# Speedy_V2_1.net
KiCad netlist of a schematic drawn in EAGLE
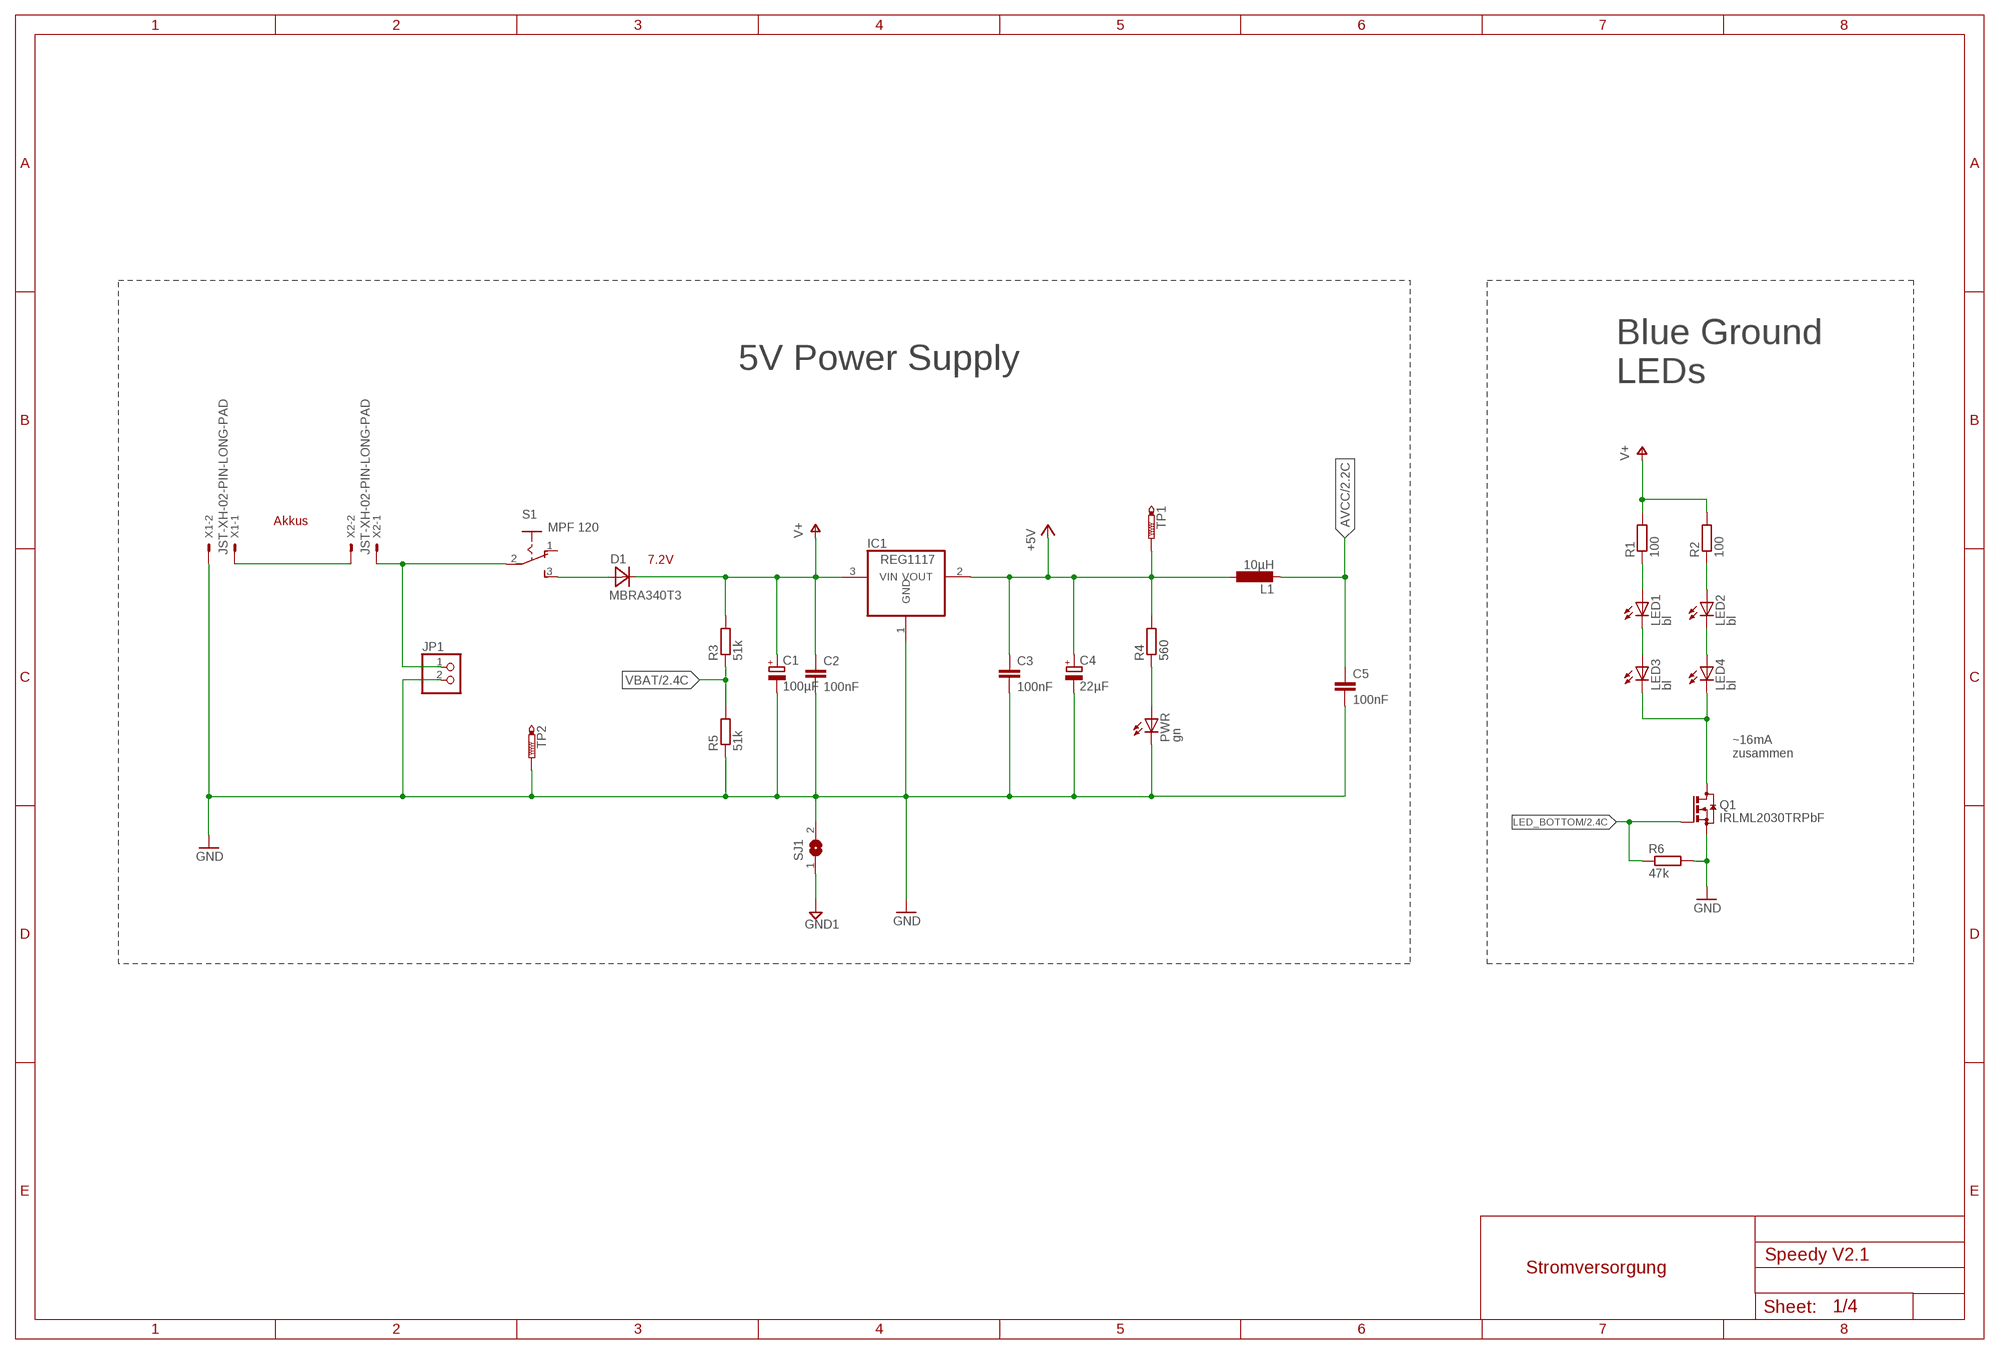
[diagram p0: schematic, sheet 1]
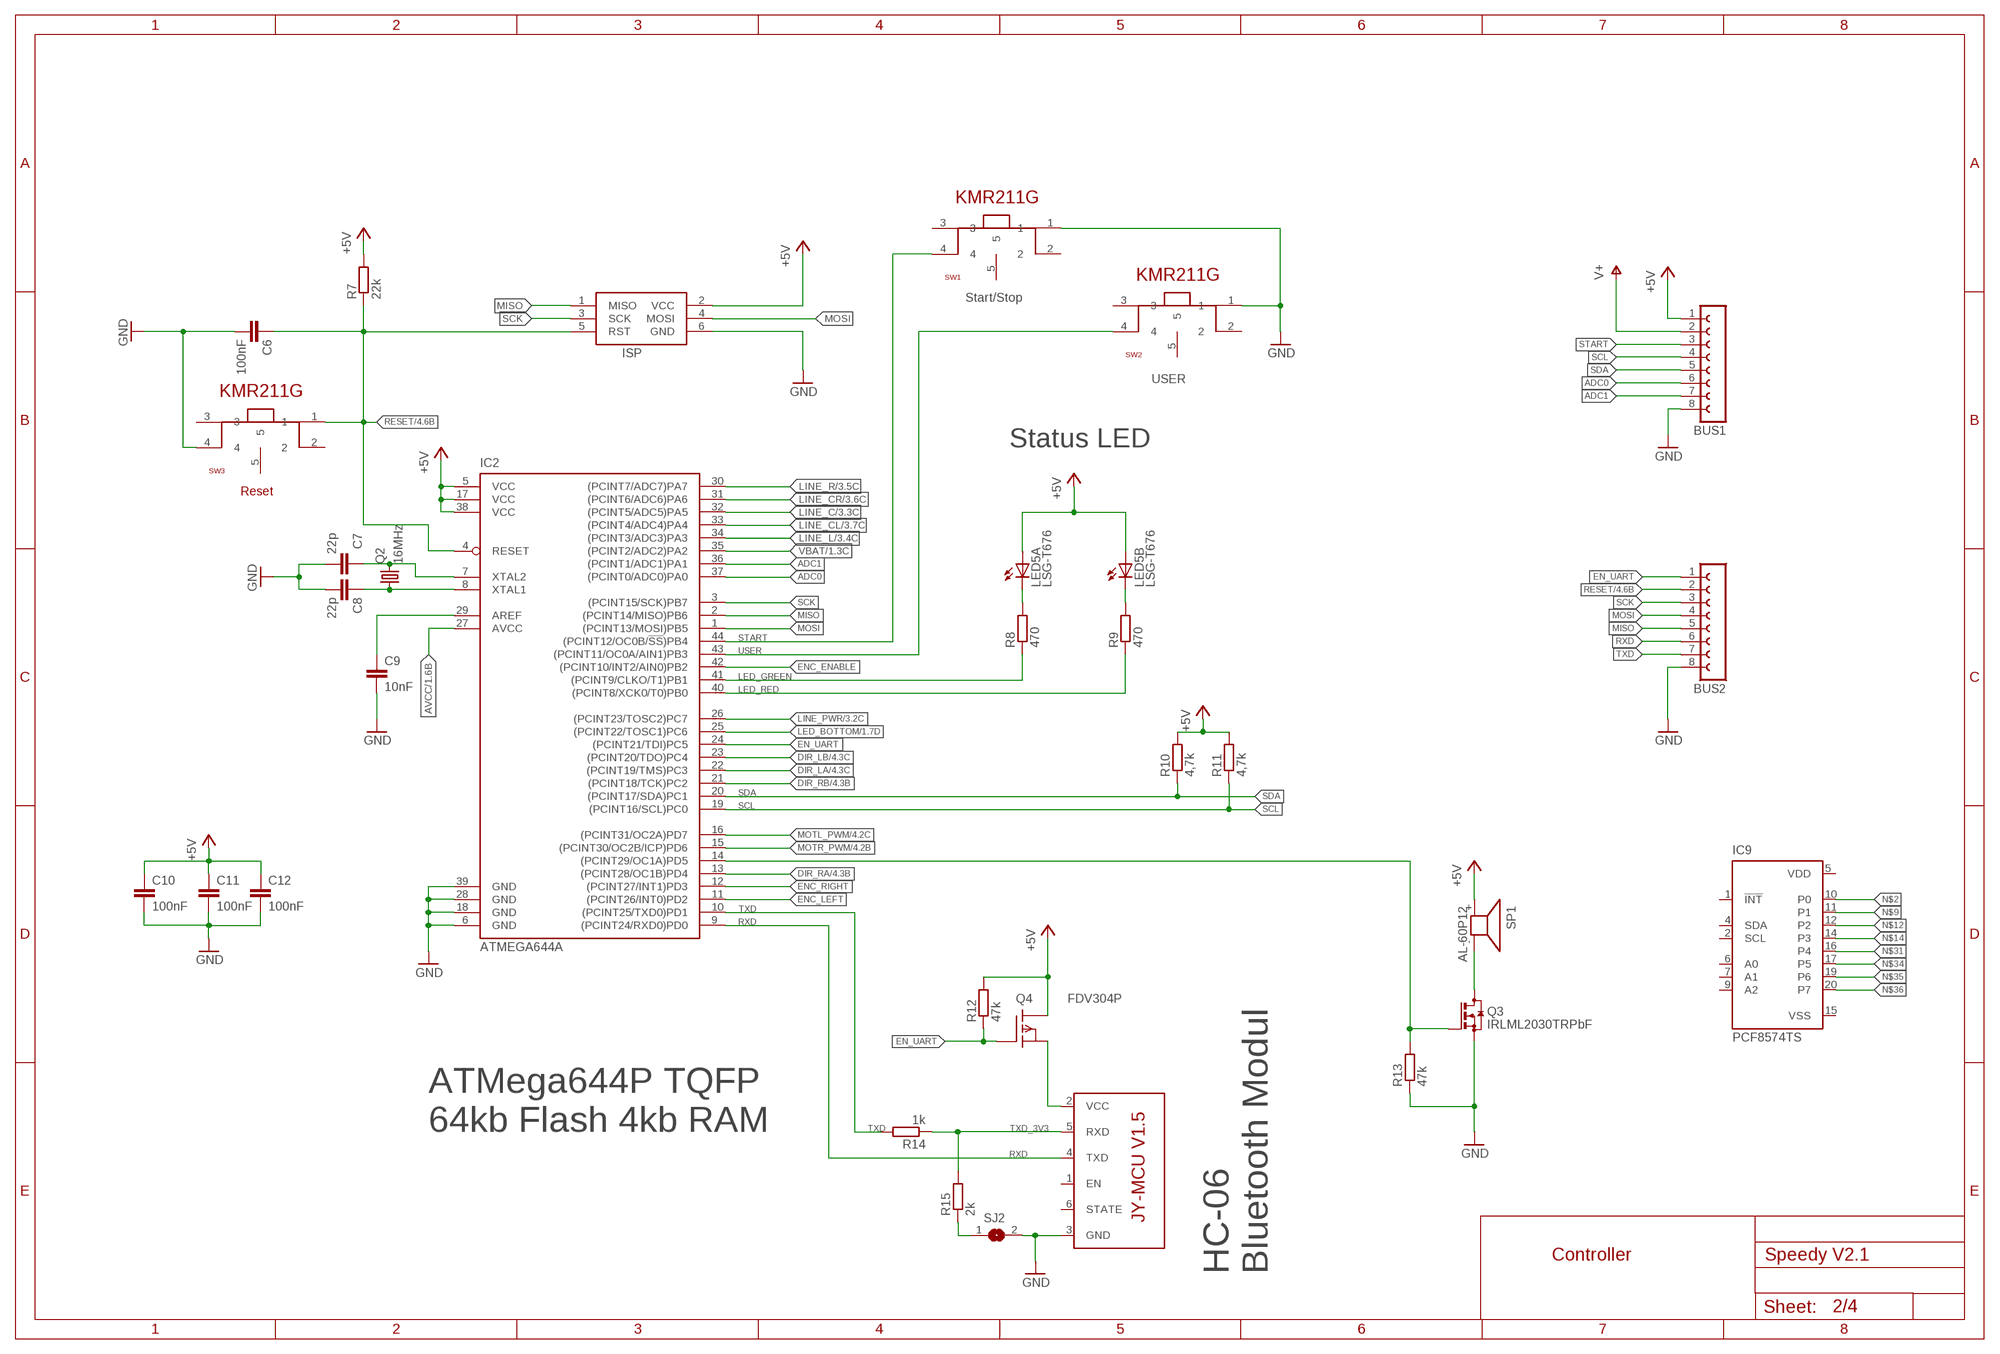
[diagram p1: schematic, sheet 2]
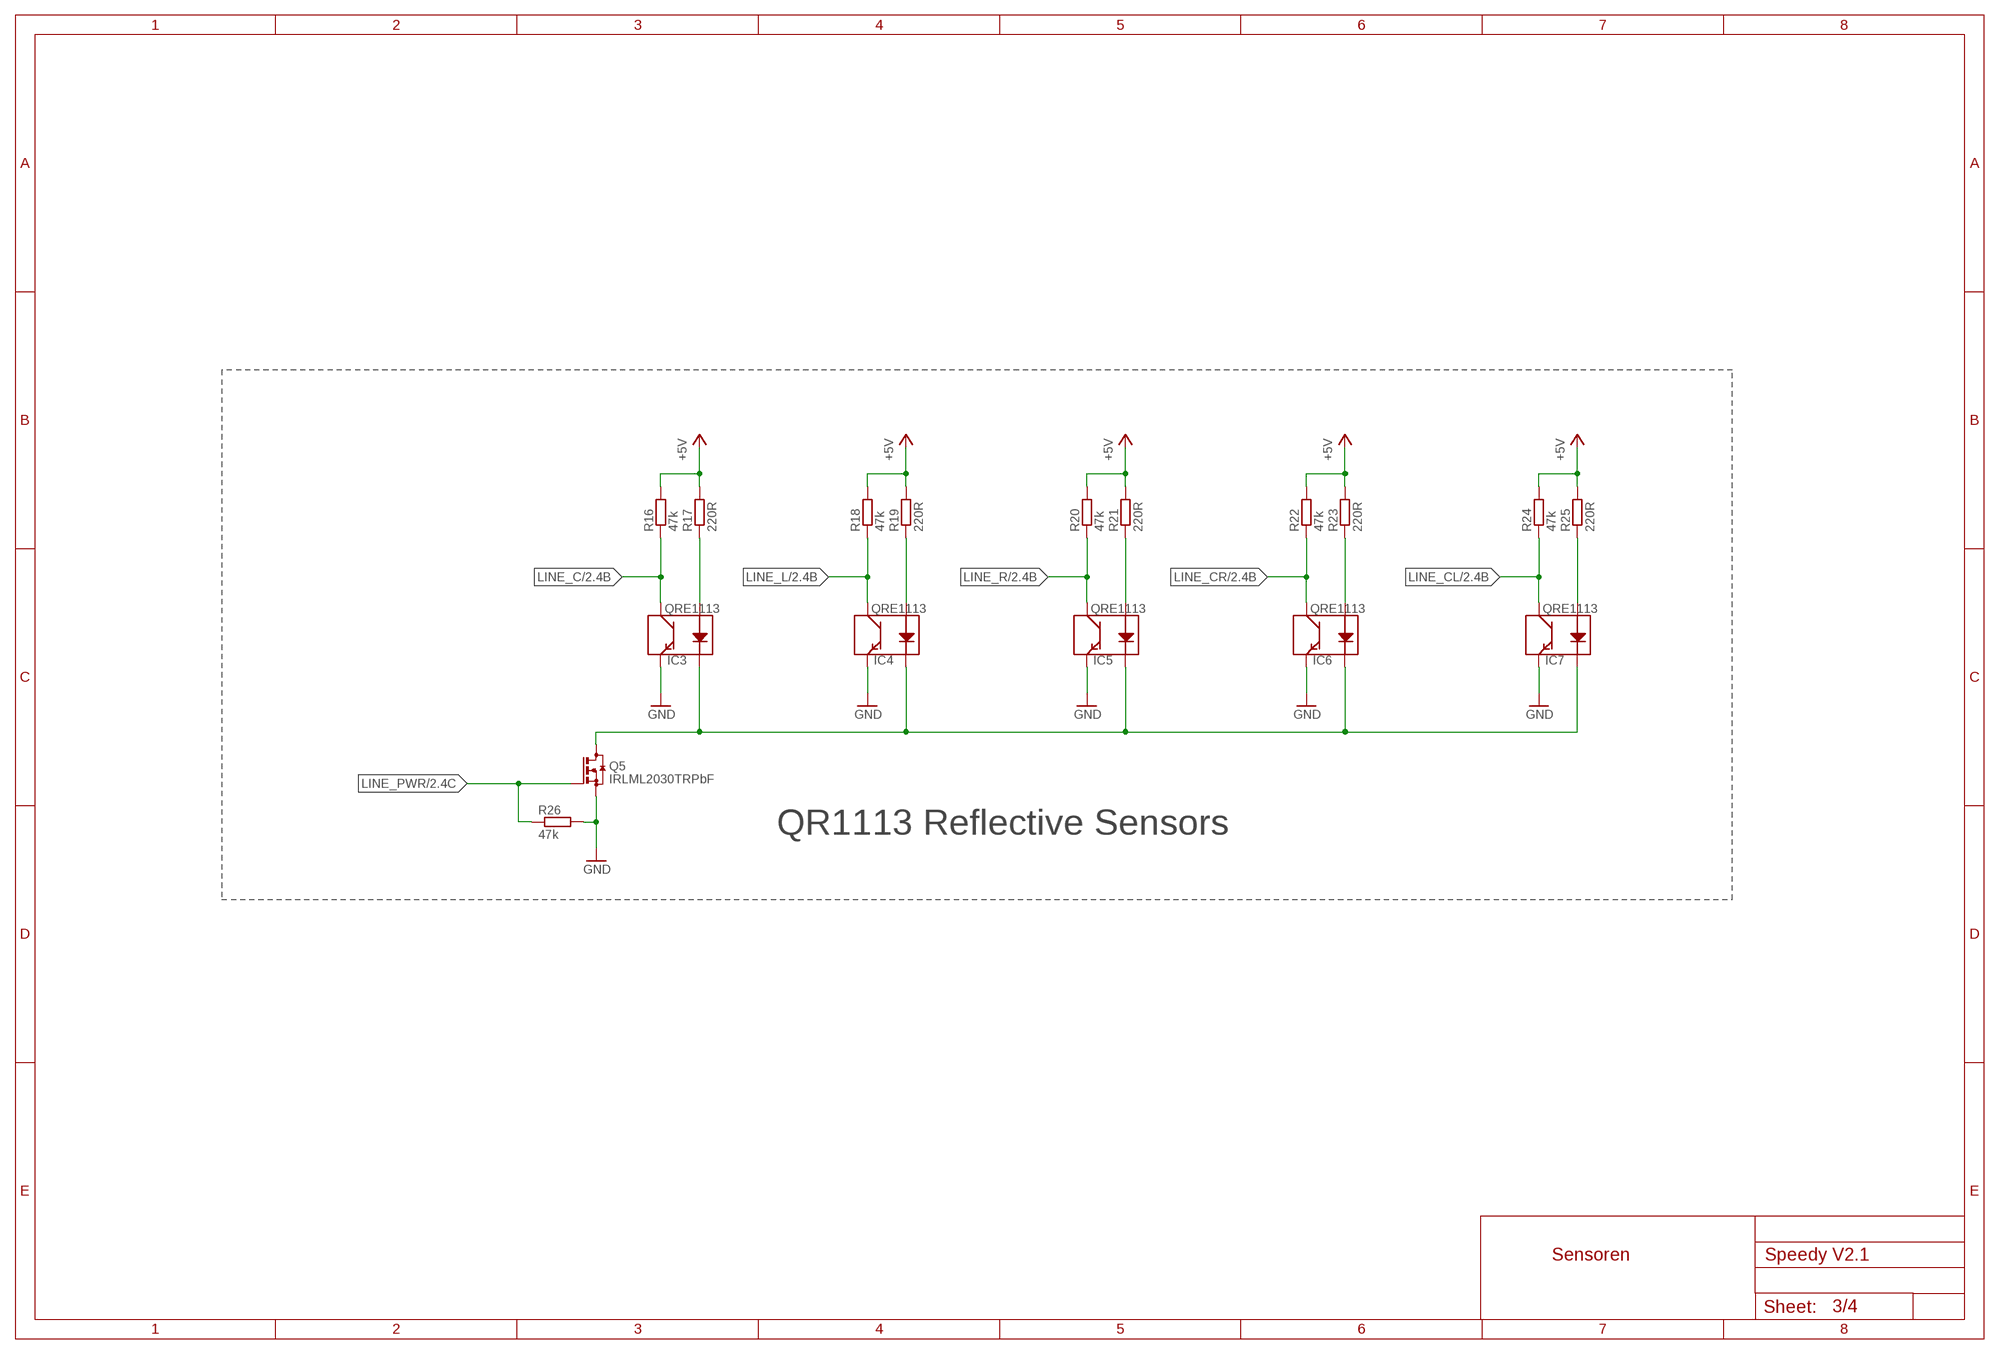
[diagram p2: schematic, sheet 3]
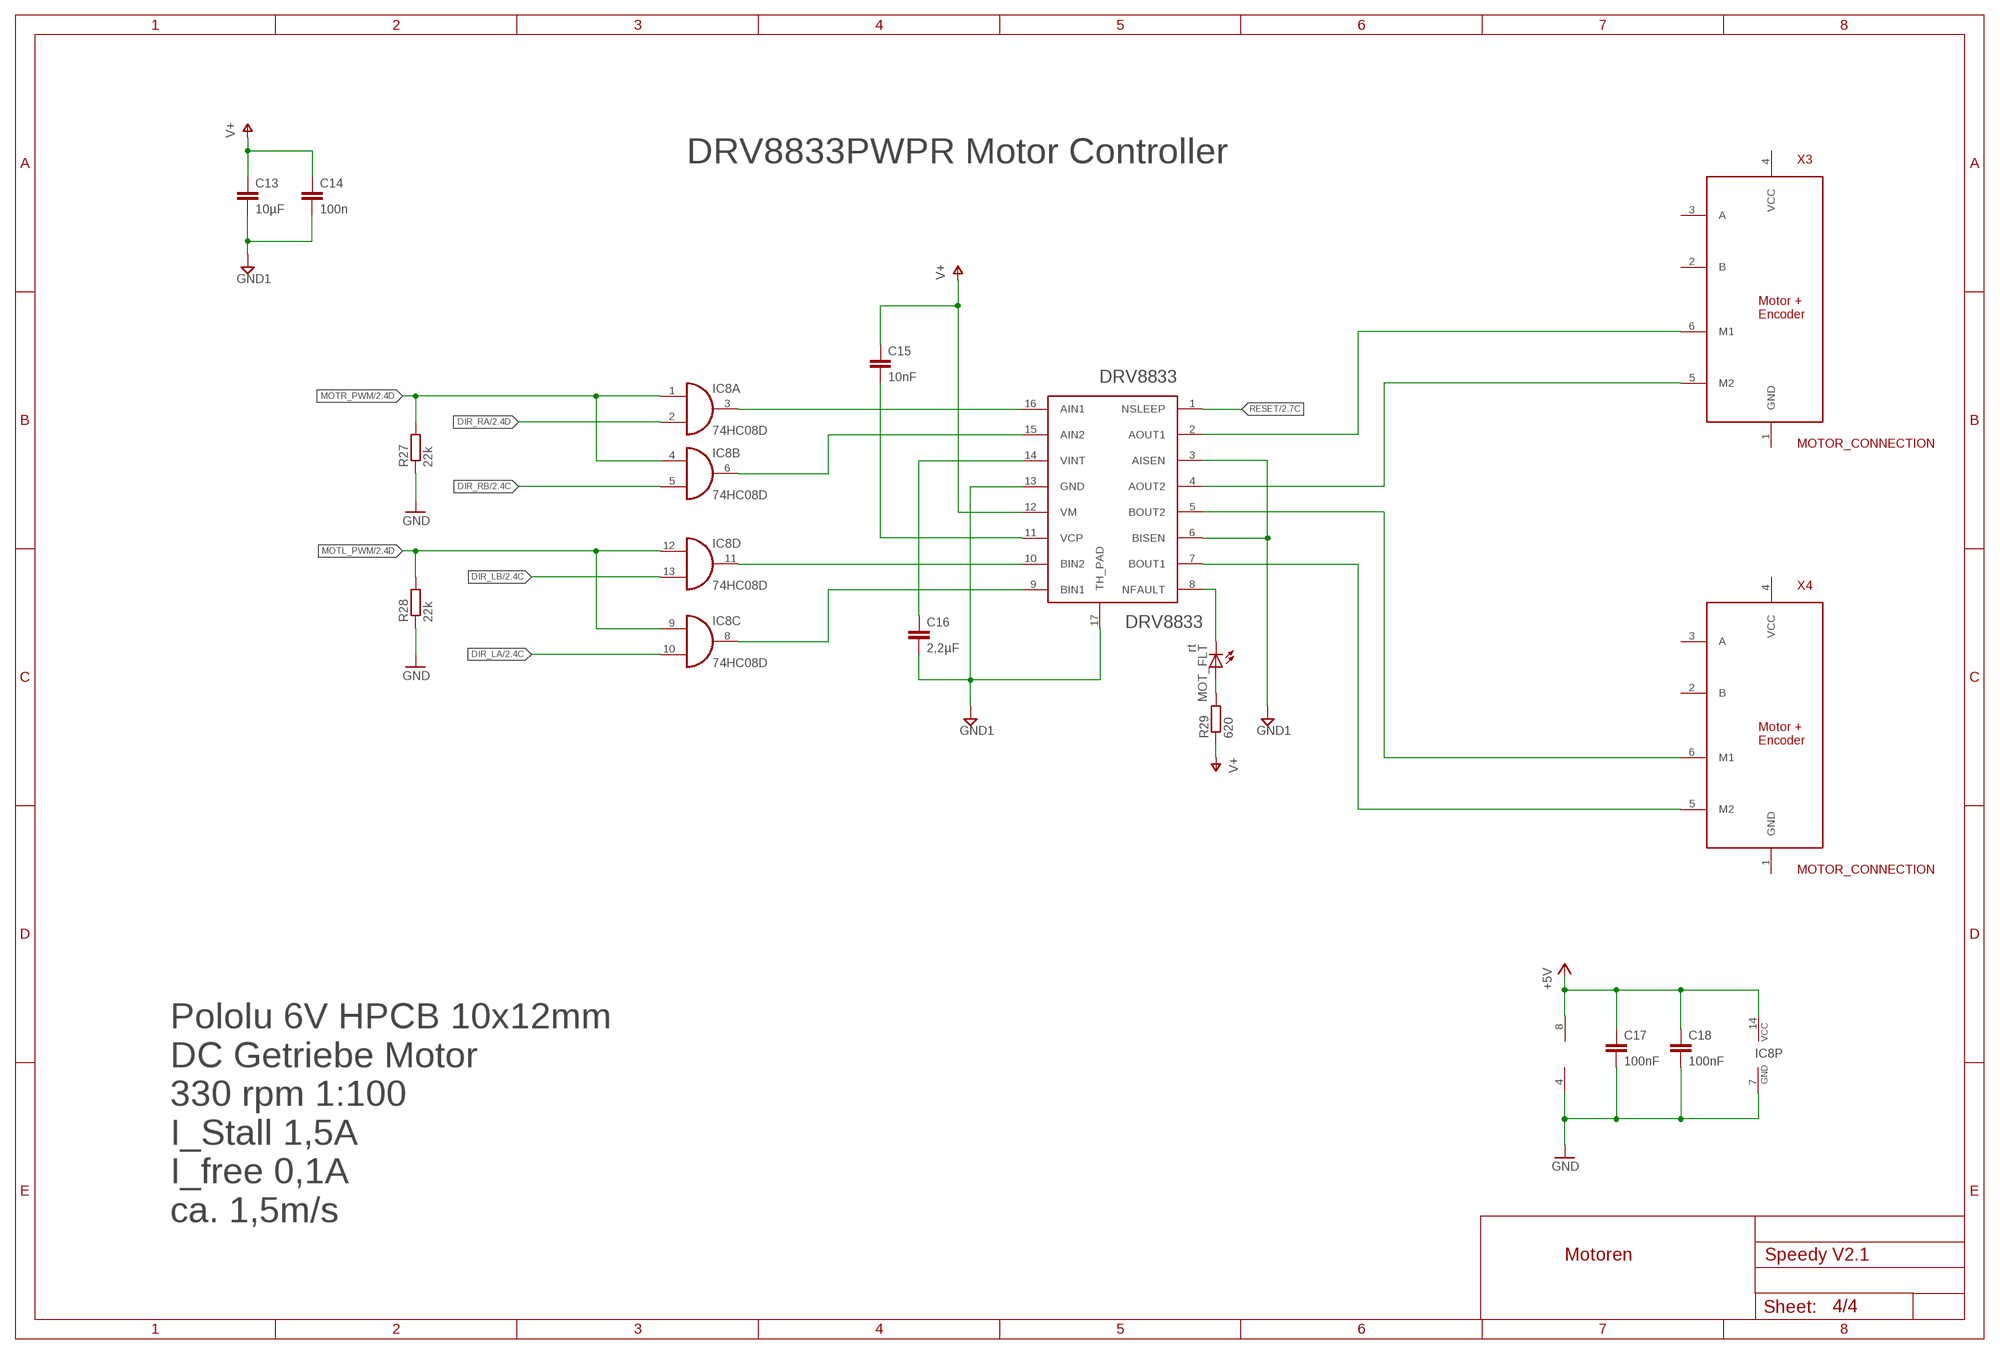
[diagram p3: schematic, sheet 4]

(export (version "E")
  (design (tool "Eeschema 10.0.6"))
  (components
    (comp (ref "C13")
      (value "10µF")
      (footprint "eagle-import:C1206")
      (libsource (lib "eagle-import") (part "C-EUC1206"))
    )
    (comp (ref "C14")
      (value "100n")
      (footprint "eagle-import:C0805")
      (libsource (lib "eagle-import") (part "C-EUC0805"))
    )
    (comp (ref "C15")
      (value "10nF")
      (footprint "eagle-import:C0805")
      (libsource (lib "eagle-import") (part "C-EUC0805"))
    )
    (comp (ref "C16")
      (value "2,2µF")
      (footprint "eagle-import:C1206")
      (libsource (lib "eagle-import") (part "C-EUC1206"))
    )
    (comp (ref "C17")
      (value "100nF")
      (footprint "eagle-import:C0805")
      (libsource (lib "eagle-import") (part "C-EUC0805"))
    )
    (comp (ref "C18")
      (value "100nF")
      (footprint "eagle-import:C0805")
      (libsource (lib "eagle-import") (part "C-EUC0805"))
    )
    (comp (ref "IC8")
      (value "74HC08D")
      (footprint "eagle-import:SO14")
      (libsource (lib "eagle-import") (part "7408DHC"))
    )
    (comp (ref "IC11")
      (value "LM358D")
      (footprint "eagle-import:SO08")
      (libsource (lib "eagle-import") (part "LM358D"))
    )
    (comp (ref "MOT_FLT")
      (value "rt")
      (footprint "eagle-import:CHIP-LED0805")
      (libsource (lib "eagle-import") (part "LEDCHIP-LED0805"))
    )
    (comp (ref "R27")
      (value "22k")
      (footprint "eagle-import:R0805")
      (libsource (lib "eagle-import") (part "R-EU_R0805"))
    )
    (comp (ref "R28")
      (value "22k")
      (footprint "eagle-import:R0805")
      (libsource (lib "eagle-import") (part "R-EU_R0805"))
    )
    (comp (ref "R29")
      (value "620")
      (footprint "eagle-import:R0805")
      (libsource (lib "eagle-import") (part "R-EU_R0805"))
    )
    (comp (ref "U3")
      (value "DRV8833")
      (footprint "eagle-import:SOP65P640X120-17N")
      (libsource (lib "eagle-import") (part "DRV8833"))
    )
    (comp (ref "X3")
      (value "MOTOR_CONNECTION")
      (footprint "eagle-import:2X03")
      (libsource (lib "eagle-import") (part "MOTOR_CONNECTION"))
    )
    (comp (ref "X4")
      (value "MOTOR_CONNECTION")
      (footprint "eagle-import:2X03")
      (libsource (lib "eagle-import") (part "MOTOR_CONNECTION"))
    )
    (comp (ref "BUS1")
      (value "FE08-1")
      (footprint "eagle-import:FE08")
      (libsource (lib "eagle-import") (part "FE08-1"))
    )
    (comp (ref "BUS2")
      (value "FE08-1")
      (footprint "eagle-import:FE08")
      (libsource (lib "eagle-import") (part "FE08-1"))
    )
    (comp (ref "C6")
      (value "100nF")
      (footprint "eagle-import:C0805")
      (libsource (lib "eagle-import") (part "C-EUC0805"))
    )
    (comp (ref "C7")
      (value "22p")
      (footprint "eagle-import:C0603")
      (libsource (lib "eagle-import") (part "C-EUC0603"))
    )
    (comp (ref "C8")
      (value "22p")
      (footprint "eagle-import:C0603")
      (libsource (lib "eagle-import") (part "C-EUC0603"))
    )
    (comp (ref "C9")
      (value "10nF")
      (footprint "eagle-import:C0603")
      (libsource (lib "eagle-import") (part "C-EUC0603"))
    )
    (comp (ref "C10")
      (value "100nF")
      (footprint "eagle-import:C0603")
      (libsource (lib "eagle-import") (part "C-EUC0603"))
    )
    (comp (ref "C11")
      (value "100nF")
      (footprint "eagle-import:C0603")
      (libsource (lib "eagle-import") (part "C-EUC0603"))
    )
    (comp (ref "C12")
      (value "100nF")
      (footprint "eagle-import:C0603")
      (libsource (lib "eagle-import") (part "C-EUC0603"))
    )
    (comp (ref "IC2")
      (value "ATMEGA644A")
      (footprint "eagle-import:TQFP44")
      (fields (field (name "MPN") "ATMEGA644PV-10AU"))
      (libsource (lib "eagle-import") (part "ATMEGA644A"))
    )
    (comp (ref "IC9")
      (value "PCF8574TS")
      (footprint "eagle-import:SSOP20")
      (fields (field (name "MPN") "PCF8574TS/3,118"))
      (libsource (lib "eagle-import") (part "PCF8574TS"))
    )
    (comp (ref "ISP")
      (value "AVRISP-6")
      (footprint "eagle-import:AVRISP")
      (libsource (lib "eagle-import") (part "AVRISP-6"))
    )
    (comp (ref "LED5")
      (value "LSG-T676")
      (footprint "eagle-import:P-LCC4-0")
      (libsource (lib "eagle-import") (part "LSG-T676"))
    )
    (comp (ref "Q2")
      (value "16MHz")
      (footprint "eagle-import:7X5MMQUARZ")
      (libsource (lib "eagle-import") (part "7X5MMMQ"))
    )
    (comp (ref "Q3")
      (value "IRLML2030TRPbF")
      (footprint "eagle-import:SOT23")
      (libsource (lib "eagle-import") (part "BSS123"))
    )
    (comp (ref "Q4")
      (value "FDV304P")
      (footprint "eagle-import:SOT23")
      (libsource (lib "eagle-import") (part "FDV304P"))
    )
    (comp (ref "R7")
      (value "22k")
      (footprint "eagle-import:R0805")
      (libsource (lib "eagle-import") (part "R-EU_R0805"))
    )
    (comp (ref "R8")
      (value "470")
      (footprint "eagle-import:R0805")
      (libsource (lib "eagle-import") (part "R-EU_R0805"))
    )
    (comp (ref "R9")
      (value "470")
      (footprint "eagle-import:R0805")
      (libsource (lib "eagle-import") (part "R-EU_R0805"))
    )
    (comp (ref "R10")
      (value "4,7k")
      (footprint "eagle-import:R0805")
      (libsource (lib "eagle-import") (part "R-EU_R0805"))
    )
    (comp (ref "R11")
      (value "4,7k")
      (footprint "eagle-import:R0805")
      (libsource (lib "eagle-import") (part "R-EU_R0805"))
    )
    (comp (ref "R12")
      (value "47k")
      (footprint "eagle-import:R0805")
      (libsource (lib "eagle-import") (part "R-EU_R0805"))
    )
    (comp (ref "R13")
      (value "47k")
      (footprint "eagle-import:R0805")
      (libsource (lib "eagle-import") (part "R-EU_R0805"))
    )
    (comp (ref "R14")
      (value "1k")
      (footprint "eagle-import:R0805")
      (libsource (lib "eagle-import") (part "R-EU_R0805"))
    )
    (comp (ref "R15")
      (value "2k")
      (footprint "eagle-import:R0805")
      (libsource (lib "eagle-import") (part "R-EU_R0805"))
    )
    (comp (ref "SJ2") (value "SJ") (footprint "eagle-import:SJ") (libsource (lib "eagle-import") (part "SJ")))
    (comp (ref "SP1")
      (value "AL-60P12")
      (footprint "eagle-import:KSS1201")
      (libsource (lib "eagle-import") (part "KSS1201"))
    )
    (comp (ref "SW1")
      (value "KMR211G_SWITCH")
      (footprint "eagle-import:KMR211G_SWITCH")
      (libsource (lib "eagle-import") (part "KMR211G_SWITCH"))
    )
    (comp (ref "SW2")
      (value "KMR211G_SWITCH")
      (footprint "eagle-import:KMR211G_SWITCH")
      (libsource (lib "eagle-import") (part "KMR211G_SWITCH"))
    )
    (comp (ref "SW3")
      (value "KMR211G_SWITCH")
      (footprint "eagle-import:KMR211G_SWITCH")
      (libsource (lib "eagle-import") (part "KMR211G_SWITCH"))
    )
    (comp (ref "U1")
      (value "BT_BOARD")
      (footprint "eagle-import:BT_BOARD")
      (libsource (lib "eagle-import") (part "BT_BOARD"))
    )
    (comp (ref "IC3")
      (value "QRE1113")
      (footprint "eagle-import:QRE1113")
      (libsource (lib "eagle-import") (part "QRE1113"))
    )
    (comp (ref "IC4")
      (value "QRE1113")
      (footprint "eagle-import:QRE1113")
      (libsource (lib "eagle-import") (part "QRE1113"))
    )
    (comp (ref "IC5")
      (value "QRE1113")
      (footprint "eagle-import:QRE1113")
      (libsource (lib "eagle-import") (part "QRE1113"))
    )
    (comp (ref "IC6")
      (value "QRE1113")
      (footprint "eagle-import:QRE1113")
      (libsource (lib "eagle-import") (part "QRE1113"))
    )
    (comp (ref "IC7")
      (value "QRE1113")
      (footprint "eagle-import:QRE1113")
      (libsource (lib "eagle-import") (part "QRE1113"))
    )
    (comp (ref "Q5")
      (value "IRLML2030TRPbF")
      (footprint "eagle-import:SOT23")
      (libsource (lib "eagle-import") (part "BSS123"))
    )
    (comp (ref "R16")
      (value "47k")
      (footprint "eagle-import:R0805")
      (libsource (lib "eagle-import") (part "R-EU_R0805"))
    )
    (comp (ref "R17")
      (value "220R")
      (footprint "eagle-import:R0805")
      (libsource (lib "eagle-import") (part "R-EU_R0805"))
    )
    (comp (ref "R18")
      (value "47k")
      (footprint "eagle-import:R0805")
      (libsource (lib "eagle-import") (part "R-EU_R0805"))
    )
    (comp (ref "R19")
      (value "220R")
      (footprint "eagle-import:R0805")
      (libsource (lib "eagle-import") (part "R-EU_R0805"))
    )
    (comp (ref "R20")
      (value "47k")
      (footprint "eagle-import:R0805")
      (libsource (lib "eagle-import") (part "R-EU_R0805"))
    )
    (comp (ref "R21")
      (value "220R")
      (footprint "eagle-import:R0805")
      (libsource (lib "eagle-import") (part "R-EU_R0805"))
    )
    (comp (ref "R22")
      (value "47k")
      (footprint "eagle-import:R0805")
      (libsource (lib "eagle-import") (part "R-EU_R0805"))
    )
    (comp (ref "R23")
      (value "220R")
      (footprint "eagle-import:R0805")
      (libsource (lib "eagle-import") (part "R-EU_R0805"))
    )
    (comp (ref "R24")
      (value "47k")
      (footprint "eagle-import:R0805")
      (libsource (lib "eagle-import") (part "R-EU_R0805"))
    )
    (comp (ref "R25")
      (value "220R")
      (footprint "eagle-import:R0805")
      (libsource (lib "eagle-import") (part "R-EU_R0805"))
    )
    (comp (ref "R26")
      (value "47k")
      (footprint "eagle-import:R0805")
      (libsource (lib "eagle-import") (part "R-EU_R0805"))
    )
    (comp (ref "C1")
      (value "100µF")
      (footprint "eagle-import:PANASONIC_D")
      (libsource (lib "eagle-import") (part "CPOL-EUD"))
    )
    (comp (ref "C2")
      (value "100nF")
      (footprint "eagle-import:C0805")
      (libsource (lib "eagle-import") (part "C-EUC0805"))
    )
    (comp (ref "C3")
      (value "100nF")
      (footprint "eagle-import:C0805")
      (libsource (lib "eagle-import") (part "C-EUC0805"))
    )
    (comp (ref "C4")
      (value "22µF")
      (footprint "eagle-import:PANASONIC_B")
      (libsource (lib "eagle-import") (part "CPOL-EUB"))
    )
    (comp (ref "C5")
      (value "100nF")
      (footprint "eagle-import:C0805")
      (libsource (lib "eagle-import") (part "C-EUC0805"))
    )
    (comp (ref "D1")
      (value "MBRA340T3")
      (footprint "eagle-import:SMA")
      (libsource (lib "eagle-import") (part "MBRA340T3"))
    )
    (comp (ref "IC1")
      (value "REG1117")
      (footprint "eagle-import:SOT223")
      (libsource (lib "eagle-import") (part "REG1117"))
    )
    (comp (ref "JP1")
      (value "PINHD-1X2")
      (footprint "eagle-import:1X02")
      (libsource (lib "eagle-import") (part "PINHD-1X2"))
    )
    (comp (ref "L1")
      (value "10µH")
      (footprint "eagle-import:C1210K")
      (libsource (lib "eagle-import") (part "L-1210"))
    )
    (comp (ref "LED1")
      (value "bl")
      (footprint "eagle-import:CHIPLED_0805")
      (libsource (lib "eagle-import") (part "LEDCHIPLED_0805"))
    )
    (comp (ref "LED2")
      (value "bl")
      (footprint "eagle-import:CHIPLED_0805")
      (libsource (lib "eagle-import") (part "LEDCHIPLED_0805"))
    )
    (comp (ref "LED3")
      (value "bl")
      (footprint "eagle-import:CHIPLED_0805")
      (libsource (lib "eagle-import") (part "LEDCHIPLED_0805"))
    )
    (comp (ref "LED4")
      (value "bl")
      (footprint "eagle-import:CHIPLED_0805")
      (libsource (lib "eagle-import") (part "LEDCHIPLED_0805"))
    )
    (comp (ref "PWR")
      (value "gn")
      (footprint "eagle-import:CHIPLED_0805")
      (libsource (lib "eagle-import") (part "LEDCHIPLED_0805"))
    )
    (comp (ref "Q1")
      (value "IRLML2030TRPbF")
      (footprint "eagle-import:SOT23")
      (libsource (lib "eagle-import") (part "BSS123"))
    )
    (comp (ref "R1")
      (value "100")
      (footprint "eagle-import:R0805")
      (libsource (lib "eagle-import") (part "R-EU_R0805"))
    )
    (comp (ref "R2")
      (value "100")
      (footprint "eagle-import:R0805")
      (libsource (lib "eagle-import") (part "R-EU_R0805"))
    )
    (comp (ref "R3")
      (value "51k")
      (footprint "eagle-import:R0805")
      (libsource (lib "eagle-import") (part "R-EU_R0805"))
    )
    (comp (ref "R4")
      (value "560")
      (footprint "eagle-import:R0805")
      (libsource (lib "eagle-import") (part "R-EU_R0805"))
    )
    (comp (ref "R5")
      (value "51k")
      (footprint "eagle-import:R0805")
      (libsource (lib "eagle-import") (part "R-EU_R0805"))
    )
    (comp (ref "R6")
      (value "47k")
      (footprint "eagle-import:R0805")
      (libsource (lib "eagle-import") (part "R-EU_R0805"))
    )
    (comp (ref "S1")
      (value "MPF 120")
      (footprint "eagle-import:255SB")
      (libsource (lib "eagle-import") (part "255SB"))
    )
    (comp (ref "SJ1") (value "SJ") (footprint "eagle-import:SJ") (libsource (lib "eagle-import") (part "SJ")))
    (comp (ref "TP1")
      (value "PTR1B1,27")
      (footprint "eagle-import:B1,27")
      (libsource (lib "eagle-import") (part "PTR1B1,27"))
    )
    (comp (ref "TP2")
      (value "PTR1PAD1-13")
      (footprint "eagle-import:P1-13")
      (libsource (lib "eagle-import") (part "PTR1PAD1-13"))
    )
    (comp (ref "X1")
      (value "JST-XH-02-PIN-LONG-PAD")
      (footprint "eagle-import:JST-XH-02-PACKAGE-LONG-PAD")
      (libsource (lib "eagle-import") (part "JST-XH-02-PIN-LONG-PAD"))
    )
    (comp (ref "X2")
      (value "JST-XH-02-PIN-LONG-PAD")
      (footprint "eagle-import:JST-XH-02-PACKAGE-LONG-PAD")
      (libsource (lib "eagle-import") (part "JST-XH-02-PIN-LONG-PAD"))
    )
  )
  (nets
    (net (code "1") (name "+5V") (class "Default")
      (node (ref "BUS1") (pin "1") (pinfunction "1_1") (pintype "passive"))
      (node (ref "C10") (pin "1") (pinfunction "1_1") (pintype "passive"))
      (node (ref "C11") (pin "1") (pinfunction "1_1") (pintype "passive"))
      (node (ref "C12") (pin "1") (pinfunction "1_1") (pintype "passive"))
      (node (ref "C17") (pin "1") (pinfunction "1_1") (pintype "passive"))
      (node (ref "C18") (pin "1") (pinfunction "1_1") (pintype "passive"))
      (node (ref "C3") (pin "1") (pinfunction "1_1") (pintype "passive"))
      (node (ref "C4") (pin "+") (pinfunction "+_+") (pintype "passive"))
      (node (ref "IC1") (pin "2") (pinfunction "VOUT_2") (pintype "output"))
      (node (ref "IC11") (pin "8") (pinfunction "V+_8") (pintype "power_in"))
      (node (ref "IC2") (pin "17") (pinfunction "VCC_17") (pintype "power_in"))
      (node (ref "IC2") (pin "38") (pinfunction "VCC_38") (pintype "power_in"))
      (node (ref "IC2") (pin "5") (pinfunction "VCC_5") (pintype "power_in"))
      (node (ref "IC8") (pin "14") (pinfunction "VCC_14") (pintype "power_in"))
      (node (ref "ISP") (pin "2") (pinfunction "VCC_2") (pintype "power_in"))
      (node (ref "L1") (pin "1") (pinfunction "1_1") (pintype "passive"))
      (node (ref "LED5") (pin "2") (pinfunction "A_2") (pintype "passive"))
      (node (ref "LED5") (pin "4") (pinfunction "A_4") (pintype "passive"))
      (node (ref "Q4") (pin "D") (pinfunction "D_D") (pintype "passive"))
      (node (ref "R10") (pin "2") (pinfunction "2_2") (pintype "passive"))
      (node (ref "R11") (pin "2") (pinfunction "2_2") (pintype "passive"))
      (node (ref "R12") (pin "2") (pinfunction "2_2") (pintype "passive"))
      (node (ref "R16") (pin "2") (pinfunction "2_2") (pintype "passive"))
      (node (ref "R17") (pin "2") (pinfunction "2_2") (pintype "passive"))
      (node (ref "R18") (pin "2") (pinfunction "2_2") (pintype "passive"))
      (node (ref "R19") (pin "2") (pinfunction "2_2") (pintype "passive"))
      (node (ref "R20") (pin "2") (pinfunction "2_2") (pintype "passive"))
      (node (ref "R21") (pin "2") (pinfunction "2_2") (pintype "passive"))
      (node (ref "R22") (pin "2") (pinfunction "2_2") (pintype "passive"))
      (node (ref "R23") (pin "2") (pinfunction "2_2") (pintype "passive"))
      (node (ref "R24") (pin "2") (pinfunction "2_2") (pintype "passive"))
      (node (ref "R25") (pin "2") (pinfunction "2_2") (pintype "passive"))
      (node (ref "R4") (pin "2") (pinfunction "2_2") (pintype "passive"))
      (node (ref "R7") (pin "2") (pinfunction "2_2") (pintype "passive"))
      (node (ref "SP1") (pin "+") (pinfunction "1_+") (pintype "passive"))
      (node (ref "TP1") (pin "TP") (pinfunction "TP_TP") (pintype "input"))
    )
    (net (code "2") (name "ADC0") (class "Default")
      (node (ref "BUS1") (pin "6") (pinfunction "6_6") (pintype "passive"))
      (node (ref "IC2") (pin "37") (pinfunction "(PCINT0/ADC0)PA0_37") (pintype "bidirectional"))
    )
    (net (code "3") (name "ADC1") (class "Default")
      (node (ref "BUS1") (pin "7") (pinfunction "7_7") (pintype "passive"))
      (node (ref "IC2") (pin "36") (pinfunction "(PCINT1/ADC1)PA1_36") (pintype "bidirectional"))
    )
    (net (code "4") (name "AVCC") (class "Default")
      (node (ref "C5") (pin "1") (pinfunction "1_1") (pintype "passive"))
      (node (ref "IC2") (pin "27") (pinfunction "AVCC_27") (pintype "power_in"))
      (node (ref "L1") (pin "2") (pinfunction "2_2") (pintype "passive"))
    )
    (net (code "5") (name "DIR_LA") (class "Default")
      (node (ref "IC2") (pin "22") (pinfunction "(PCINT19/TMS)PC3_22") (pintype "output"))
      (node (ref "IC8") (pin "10") (pinfunction "I1_10") (pintype "input"))
    )
    (net (code "6") (name "DIR_LB") (class "Default")
      (node (ref "IC2") (pin "23") (pinfunction "(PCINT20/TDO)PC4_23") (pintype "output"))
      (node (ref "IC8") (pin "13") (pinfunction "I1_13") (pintype "input"))
    )
    (net (code "7") (name "DIR_RA") (class "Default")
      (node (ref "IC2") (pin "13") (pinfunction "(PCINT28/OC1B)PD4_13") (pintype "bidirectional"))
      (node (ref "IC8") (pin "2") (pinfunction "I1_2") (pintype "input"))
    )
    (net (code "8") (name "DIR_RB") (class "Default")
      (node (ref "IC2") (pin "21") (pinfunction "(PCINT18/TCK)PC2_21") (pintype "output"))
      (node (ref "IC8") (pin "5") (pinfunction "I1_5") (pintype "input"))
    )
    (net (code "9") (name "ENC_ENABLE") (class "Default")
      (node (ref "IC2") (pin "42") (pinfunction "(PCINT10/INT2/AIN0)PB2_42") (pintype "bidirectional"))
    )
    (net (code "10") (name "ENC_LEFT") (class "Default")
      (node (ref "IC2") (pin "11") (pinfunction "(PCINT26/INT0)PD2_11") (pintype "bidirectional"))
    )
    (net (code "11") (name "ENC_RIGHT") (class "Default")
      (node (ref "IC2") (pin "12") (pinfunction "(PCINT27/INT1)PD3_12") (pintype "bidirectional"))
    )
    (net (code "12") (name "EN_UART") (class "Default")
      (node (ref "BUS2") (pin "1") (pinfunction "1_1") (pintype "passive"))
      (node (ref "IC2") (pin "24") (pinfunction "(PCINT21/TDI)PC5_24") (pintype "output"))
      (node (ref "Q4") (pin "G") (pinfunction "G_G") (pintype "passive"))
      (node (ref "R12") (pin "1") (pinfunction "1_1") (pintype "passive"))
    )
    (net (code "13") (name "GND") (class "Default")
      (node (ref "BUS1") (pin "8") (pinfunction "8_8") (pintype "passive"))
      (node (ref "BUS2") (pin "8") (pinfunction "8_8") (pintype "passive"))
      (node (ref "C1") (pin "-") (pinfunction "-_-") (pintype "passive"))
      (node (ref "C10") (pin "2") (pinfunction "2_2") (pintype "passive"))
      (node (ref "C11") (pin "2") (pinfunction "2_2") (pintype "passive"))
      (node (ref "C12") (pin "2") (pinfunction "2_2") (pintype "passive"))
      (node (ref "C17") (pin "2") (pinfunction "2_2") (pintype "passive"))
      (node (ref "C18") (pin "2") (pinfunction "2_2") (pintype "passive"))
      (node (ref "C2") (pin "2") (pinfunction "2_2") (pintype "passive"))
      (node (ref "C3") (pin "2") (pinfunction "2_2") (pintype "passive"))
      (node (ref "C4") (pin "-") (pinfunction "-_-") (pintype "passive"))
      (node (ref "C5") (pin "2") (pinfunction "2_2") (pintype "passive"))
      (node (ref "C6") (pin "2") (pinfunction "2_2") (pintype "passive"))
      (node (ref "C7") (pin "2") (pinfunction "2_2") (pintype "passive"))
      (node (ref "C8") (pin "2") (pinfunction "2_2") (pintype "passive"))
      (node (ref "C9") (pin "2") (pinfunction "2_2") (pintype "passive"))
      (node (ref "IC1") (pin "1") (pinfunction "GND_1") (pintype "power_in"))
      (node (ref "IC11") (pin "4") (pinfunction "V-_4") (pintype "power_in"))
      (node (ref "IC2") (pin "18") (pinfunction "GND_18") (pintype "power_in"))
      (node (ref "IC2") (pin "28") (pinfunction "GND_28") (pintype "power_in"))
      (node (ref "IC2") (pin "39") (pinfunction "GND_39") (pintype "power_in"))
      (node (ref "IC2") (pin "6") (pinfunction "GND_6") (pintype "power_in"))
      (node (ref "IC3") (pin "4") (pinfunction "E_4") (pintype "bidirectional"))
      (node (ref "IC4") (pin "4") (pinfunction "E_4") (pintype "bidirectional"))
      (node (ref "IC5") (pin "4") (pinfunction "E_4") (pintype "bidirectional"))
      (node (ref "IC6") (pin "4") (pinfunction "E_4") (pintype "bidirectional"))
      (node (ref "IC7") (pin "4") (pinfunction "E_4") (pintype "bidirectional"))
      (node (ref "IC8") (pin "7") (pinfunction "GND_7") (pintype "power_in"))
      (node (ref "ISP") (pin "6") (pinfunction "GND_6") (pintype "power_in"))
      (node (ref "JP1") (pin "2") (pinfunction "2_2") (pintype "passive"))
      (node (ref "PWR") (pin "C") (pinfunction "C_C") (pintype "passive"))
      (node (ref "Q1") (pin "2") (pinfunction "S_2") (pintype "passive"))
      (node (ref "Q3") (pin "2") (pinfunction "S_2") (pintype "passive"))
      (node (ref "Q5") (pin "2") (pinfunction "S_2") (pintype "passive"))
      (node (ref "R13") (pin "1") (pinfunction "1_1") (pintype "passive"))
      (node (ref "R26") (pin "2") (pinfunction "2_2") (pintype "passive"))
      (node (ref "R27") (pin "1") (pinfunction "1_1") (pintype "passive"))
      (node (ref "R28") (pin "1") (pinfunction "1_1") (pintype "passive"))
      (node (ref "R5") (pin "1") (pinfunction "1_1") (pintype "passive"))
      (node (ref "R6") (pin "2") (pinfunction "2_2") (pintype "passive"))
      (node (ref "SJ1") (pin "2") (pinfunction "2_2") (pintype "passive"))
      (node (ref "SJ2") (pin "2") (pinfunction "2_2") (pintype "passive"))
      (node (ref "SW1") (pin "1") (pinfunction "1_1") (pintype "bidirectional"))
      (node (ref "SW2") (pin "1") (pinfunction "1_1") (pintype "bidirectional"))
      (node (ref "SW3") (pin "4") (pinfunction "4_4") (pintype "bidirectional"))
      (node (ref "TP2") (pin "TP") (pinfunction "TP_TP") (pintype "input"))
      (node (ref "U1") (pin "3") (pinfunction "GND_3") (pintype "bidirectional"))
      (node (ref "X1") (pin "2") (pinfunction "S_2") (pintype "passive"))
    )
    (net (code "14") (name "GND1") (class "Default")
      (node (ref "C13") (pin "2") (pinfunction "2_2") (pintype "passive"))
      (node (ref "C14") (pin "2") (pinfunction "2_2") (pintype "passive"))
      (node (ref "C16") (pin "2") (pinfunction "2_2") (pintype "passive"))
      (node (ref "SJ1") (pin "1") (pinfunction "1_1") (pintype "passive"))
      (node (ref "U3") (pin "13") (pinfunction "GND_13") (pintype "bidirectional"))
      (node (ref "U3") (pin "17") (pinfunction "TH_PAD_17") (pintype "bidirectional"))
      (node (ref "U3") (pin "3") (pinfunction "AISEN_3") (pintype "bidirectional"))
      (node (ref "U3") (pin "6") (pinfunction "BISEN_6") (pintype "bidirectional"))
    )
    (net (code "15") (name "LED_BOTTOM") (class "Default")
      (node (ref "IC2") (pin "25") (pinfunction "(PCINT22/TOSC1)PC6_25") (pintype "output"))
      (node (ref "Q1") (pin "1") (pinfunction "G_1") (pintype "passive"))
      (node (ref "R6") (pin "1") (pinfunction "1_1") (pintype "passive"))
    )
    (net (code "16") (name "LED_GREEN") (class "Default")
      (node (ref "IC2") (pin "41") (pinfunction "(PCINT9/CLKO/T1)PB1_41") (pintype "bidirectional"))
      (node (ref "R8") (pin "1") (pinfunction "1_1") (pintype "passive"))
    )
    (net (code "17") (name "LED_RED") (class "Default")
      (node (ref "IC2") (pin "40") (pinfunction "(PCINT8/XCK0/T0)PB0_40") (pintype "bidirectional"))
      (node (ref "R9") (pin "1") (pinfunction "1_1") (pintype "passive"))
    )
    (net (code "18") (name "LINE_C") (class "Default")
      (node (ref "IC2") (pin "32") (pinfunction "(PCINT5/ADC5)PA5_32") (pintype "bidirectional"))
      (node (ref "IC3") (pin "3") (pinfunction "C_3") (pintype "bidirectional"))
      (node (ref "R16") (pin "1") (pinfunction "1_1") (pintype "passive"))
    )
    (net (code "19") (name "LINE_CL") (class "Default")
      (node (ref "IC2") (pin "33") (pinfunction "(PCINT4/ADC4)PA4_33") (pintype "bidirectional"))
      (node (ref "IC7") (pin "3") (pinfunction "C_3") (pintype "bidirectional"))
      (node (ref "R24") (pin "1") (pinfunction "1_1") (pintype "passive"))
    )
    (net (code "20") (name "LINE_CR") (class "Default")
      (node (ref "IC2") (pin "31") (pinfunction "(PCINT6/ADC6)PA6_31") (pintype "bidirectional"))
      (node (ref "IC6") (pin "3") (pinfunction "C_3") (pintype "bidirectional"))
      (node (ref "R22") (pin "1") (pinfunction "1_1") (pintype "passive"))
    )
    (net (code "21") (name "LINE_L") (class "Default")
      (node (ref "IC2") (pin "34") (pinfunction "(PCINT3/ADC3)PA3_34") (pintype "bidirectional"))
      (node (ref "IC4") (pin "3") (pinfunction "C_3") (pintype "bidirectional"))
      (node (ref "R18") (pin "1") (pinfunction "1_1") (pintype "passive"))
    )
    (net (code "22") (name "LINE_PWR") (class "Default")
      (node (ref "IC2") (pin "26") (pinfunction "(PCINT23/TOSC2)PC7_26") (pintype "output"))
      (node (ref "Q5") (pin "1") (pinfunction "G_1") (pintype "passive"))
      (node (ref "R26") (pin "1") (pinfunction "1_1") (pintype "passive"))
    )
    (net (code "23") (name "LINE_R") (class "Default")
      (node (ref "IC2") (pin "30") (pinfunction "(PCINT7/ADC7)PA7_30") (pintype "bidirectional"))
      (node (ref "IC5") (pin "3") (pinfunction "C_3") (pintype "bidirectional"))
      (node (ref "R20") (pin "1") (pinfunction "1_1") (pintype "passive"))
    )
    (net (code "24") (name "MISO") (class "Default")
      (node (ref "BUS2") (pin "5") (pinfunction "5_5") (pintype "passive"))
      (node (ref "IC2") (pin "2") (pinfunction "(PCINT14/MISO)PB6_2") (pintype "bidirectional"))
      (node (ref "ISP") (pin "1") (pinfunction "MISO_1") (pintype "input"))
    )
    (net (code "25") (name "MOSI") (class "Default")
      (node (ref "BUS2") (pin "4") (pinfunction "4_4") (pintype "passive"))
      (node (ref "IC2") (pin "1") (pinfunction "(PCINT13/MOSI)PB5_1") (pintype "bidirectional"))
      (node (ref "ISP") (pin "4") (pinfunction "MOSI_4") (pintype "output"))
    )
    (net (code "26") (name "MOTL_PWM") (class "Default")
      (node (ref "IC2") (pin "16") (pinfunction "(PCINT31/OC2A)PD7_16") (pintype "bidirectional"))
      (node (ref "IC8") (pin "12") (pinfunction "I0_12") (pintype "input"))
      (node (ref "IC8") (pin "9") (pinfunction "I0_9") (pintype "input"))
      (node (ref "R28") (pin "2") (pinfunction "2_2") (pintype "passive"))
    )
    (net (code "27") (name "MOTR_PWM") (class "Default")
      (node (ref "IC2") (pin "15") (pinfunction "(PCINT30/OC2B/ICP)PD6_15") (pintype "bidirectional"))
      (node (ref "IC8") (pin "1") (pinfunction "I0_1") (pintype "input"))
      (node (ref "IC8") (pin "4") (pinfunction "I0_4") (pintype "input"))
      (node (ref "R27") (pin "2") (pinfunction "2_2") (pintype "passive"))
    )
    (net (code "28") (name "N$2") (class "Default")
      (node (ref "IC9") (pin "10") (pinfunction "P0_10") (pintype "bidirectional"))
    )
    (net (code "29") (name "N$9") (class "Default")
      (node (ref "IC9") (pin "11") (pinfunction "P1_11") (pintype "bidirectional"))
    )
    (net (code "30") (name "N$12") (class "Default")
      (node (ref "IC9") (pin "12") (pinfunction "P2_12") (pintype "bidirectional"))
    )
    (net (code "31") (name "N$14") (class "Default")
      (node (ref "IC9") (pin "14") (pinfunction "P3_14") (pintype "bidirectional"))
    )
    (net (code "32") (name "N$31") (class "Default")
      (node (ref "IC9") (pin "16") (pinfunction "P4_16") (pintype "bidirectional"))
    )
    (net (code "33") (name "N$34") (class "Default")
      (node (ref "IC9") (pin "17") (pinfunction "P5_17") (pintype "bidirectional"))
    )
    (net (code "34") (name "N$35") (class "Default")
      (node (ref "IC9") (pin "19") (pinfunction "P6_19") (pintype "bidirectional"))
    )
    (net (code "35") (name "N$36") (class "Default")
      (node (ref "IC9") (pin "20") (pinfunction "P7_20") (pintype "bidirectional"))
    )
    (net (code "36") (name "Net-(IC2-(PCINT29{slash}OC1A)PD5)") (class "Default")
      (node (ref "IC2") (pin "14") (pinfunction "(PCINT29/OC1A)PD5_14") (pintype "bidirectional"))
      (node (ref "Q3") (pin "1") (pinfunction "G_1") (pintype "passive"))
      (node (ref "R13") (pin "2") (pinfunction "2_2") (pintype "passive"))
    )
    (net (code "37") (name "Net-(IC2-AREF)") (class "Default")
      (node (ref "C9") (pin "1") (pinfunction "1_1") (pintype "passive"))
      (node (ref "IC2") (pin "29") (pinfunction "AREF_29") (pintype "passive"))
    )
    (net (code "38") (name "Net-(IC2-XTAL1)") (class "Default")
      (node (ref "C8") (pin "1") (pinfunction "1_1") (pintype "passive"))
      (node (ref "IC2") (pin "8") (pinfunction "XTAL1_8") (pintype "bidirectional"))
      (node (ref "Q2") (pin "P$1") (pinfunction "1_P$1") (pintype "passive"))
    )
    (net (code "39") (name "Net-(IC2-XTAL2)") (class "Default")
      (node (ref "C7") (pin "1") (pinfunction "1_1") (pintype "passive"))
      (node (ref "IC2") (pin "7") (pinfunction "XTAL2_7") (pintype "bidirectional"))
      (node (ref "Q2") (pin "P$3") (pinfunction "2_P$3") (pintype "passive"))
    )
    (net (code "40") (name "Net-(IC3-A)") (class "Default")
      (node (ref "IC3") (pin "1") (pinfunction "A_1") (pintype "bidirectional"))
      (node (ref "R17") (pin "1") (pinfunction "1_1") (pintype "passive"))
    )
    (net (code "41") (name "Net-(IC3-K)") (class "Default")
      (node (ref "IC3") (pin "2") (pinfunction "K_2") (pintype "bidirectional"))
      (node (ref "IC4") (pin "2") (pinfunction "K_2") (pintype "bidirectional"))
      (node (ref "IC5") (pin "2") (pinfunction "K_2") (pintype "bidirectional"))
      (node (ref "IC6") (pin "2") (pinfunction "K_2") (pintype "bidirectional"))
      (node (ref "IC7") (pin "2") (pinfunction "K_2") (pintype "bidirectional"))
      (node (ref "Q5") (pin "3") (pinfunction "D_3") (pintype "passive"))
    )
    (net (code "42") (name "Net-(IC4-A)") (class "Default")
      (node (ref "IC4") (pin "1") (pinfunction "A_1") (pintype "bidirectional"))
      (node (ref "R19") (pin "1") (pinfunction "1_1") (pintype "passive"))
    )
    (net (code "43") (name "Net-(IC5-A)") (class "Default")
      (node (ref "IC5") (pin "1") (pinfunction "A_1") (pintype "bidirectional"))
      (node (ref "R21") (pin "1") (pinfunction "1_1") (pintype "passive"))
    )
    (net (code "44") (name "Net-(IC6-A)") (class "Default")
      (node (ref "IC6") (pin "1") (pinfunction "A_1") (pintype "bidirectional"))
      (node (ref "R23") (pin "1") (pinfunction "1_1") (pintype "passive"))
    )
    (net (code "45") (name "Net-(IC7-A)") (class "Default")
      (node (ref "IC7") (pin "1") (pinfunction "A_1") (pintype "bidirectional"))
      (node (ref "R25") (pin "1") (pinfunction "1_1") (pintype "passive"))
    )
    (net (code "46") (name "Net-(IC8A-O)") (class "Default")
      (node (ref "IC8") (pin "3") (pinfunction "O_3") (pintype "output"))
      (node (ref "U3") (pin "16") (pinfunction "AIN1_16") (pintype "bidirectional"))
    )
    (net (code "47") (name "Net-(IC8B-O)") (class "Default")
      (node (ref "IC8") (pin "6") (pinfunction "O_6") (pintype "output"))
      (node (ref "U3") (pin "15") (pinfunction "AIN2_15") (pintype "bidirectional"))
    )
    (net (code "48") (name "Net-(IC8C-O)") (class "Default")
      (node (ref "IC8") (pin "8") (pinfunction "O_8") (pintype "output"))
      (node (ref "U3") (pin "9") (pinfunction "BIN1_9") (pintype "bidirectional"))
    )
    (net (code "49") (name "Net-(IC8D-O)") (class "Default")
      (node (ref "IC8") (pin "11") (pinfunction "O_11") (pintype "output"))
      (node (ref "U3") (pin "10") (pinfunction "BIN2_10") (pintype "bidirectional"))
    )
    (net (code "50") (name "Net-(LED1-PadA)") (class "Default")
      (node (ref "LED1") (pin "A") (pinfunction "A_A") (pintype "passive"))
      (node (ref "R1") (pin "1") (pinfunction "1_1") (pintype "passive"))
    )
    (net (code "51") (name "Net-(LED1-PadC)") (class "Default")
      (node (ref "LED1") (pin "C") (pinfunction "C_C") (pintype "passive"))
      (node (ref "LED3") (pin "A") (pinfunction "A_A") (pintype "passive"))
    )
    (net (code "52") (name "Net-(LED2-PadA)") (class "Default")
      (node (ref "LED2") (pin "A") (pinfunction "A_A") (pintype "passive"))
      (node (ref "R2") (pin "1") (pinfunction "1_1") (pintype "passive"))
    )
    (net (code "53") (name "Net-(LED2-PadC)") (class "Default")
      (node (ref "LED2") (pin "C") (pinfunction "C_C") (pintype "passive"))
      (node (ref "LED4") (pin "A") (pinfunction "A_A") (pintype "passive"))
    )
    (net (code "54") (name "Net-(LED5A-C)") (class "Default")
      (node (ref "LED5") (pin "1") (pinfunction "C_1") (pintype "passive"))
      (node (ref "R8") (pin "2") (pinfunction "2_2") (pintype "passive"))
    )
    (net (code "55") (name "Net-(LED5B-C)") (class "Default")
      (node (ref "LED5") (pin "3") (pinfunction "C_3") (pintype "passive"))
      (node (ref "R9") (pin "2") (pinfunction "2_2") (pintype "passive"))
    )
    (net (code "56") (name "Net-(MOT_FLT-PadA)") (class "Default")
      (node (ref "MOT_FLT") (pin "A") (pinfunction "A_A") (pintype "passive"))
      (node (ref "R29") (pin "2") (pinfunction "2_2") (pintype "passive"))
    )
    (net (code "57") (name "Net-(PWR-PadA)") (class "Default")
      (node (ref "PWR") (pin "A") (pinfunction "A_A") (pintype "passive"))
      (node (ref "R4") (pin "1") (pinfunction "1_1") (pintype "passive"))
    )
    (net (code "58") (name "Net-(Q1-D)") (class "Default")
      (node (ref "LED3") (pin "C") (pinfunction "C_C") (pintype "passive"))
      (node (ref "LED4") (pin "C") (pinfunction "C_C") (pintype "passive"))
      (node (ref "Q1") (pin "3") (pinfunction "D_3") (pintype "passive"))
    )
    (net (code "59") (name "Net-(Q3-D)") (class "Default")
      (node (ref "Q3") (pin "3") (pinfunction "D_3") (pintype "passive"))
      (node (ref "SP1") (pin "-") (pinfunction "2_-") (pintype "passive"))
    )
    (net (code "60") (name "Net-(R15-Pad1)") (class "Default")
      (node (ref "R15") (pin "1") (pinfunction "1_1") (pintype "passive"))
      (node (ref "SJ2") (pin "1") (pinfunction "1_1") (pintype "passive"))
    )
    (net (code "61") (name "Net-(S1-P)") (class "Default")
      (node (ref "JP1") (pin "1") (pinfunction "1_1") (pintype "passive"))
      (node (ref "S1") (pin "2") (pinfunction "P_2") (pintype "passive"))
      (node (ref "X2") (pin "1") (pinfunction "S_1") (pintype "passive"))
    )
    (net (code "62") (name "Net-(S1-S)") (class "Default")
      (node (ref "D1") (pin "A") (pinfunction "A_A") (pintype "passive"))
      (node (ref "S1") (pin "3") (pinfunction "S_3") (pintype "passive"))
    )
    (net (code "63") (name "Net-(U1-VCC)") (class "Default")
      (node (ref "Q4") (pin "S") (pinfunction "S_S") (pintype "passive"))
      (node (ref "U1") (pin "2") (pinfunction "VCC_2") (pintype "bidirectional"))
    )
    (net (code "64") (name "Net-(U3-AOUT1)") (class "Default")
      (node (ref "U3") (pin "2") (pinfunction "AOUT1_2") (pintype "bidirectional"))
      (node (ref "X3") (pin "6") (pinfunction "M1_6") (pintype "bidirectional"))
    )
    (net (code "65") (name "Net-(U3-AOUT2)") (class "Default")
      (node (ref "U3") (pin "4") (pinfunction "AOUT2_4") (pintype "bidirectional"))
      (node (ref "X3") (pin "5") (pinfunction "M2_5") (pintype "bidirectional"))
    )
    (net (code "66") (name "Net-(U3-BOUT1)") (class "Default")
      (node (ref "U3") (pin "7") (pinfunction "BOUT1_7") (pintype "bidirectional"))
      (node (ref "X4") (pin "5") (pinfunction "M2_5") (pintype "bidirectional"))
    )
    (net (code "67") (name "Net-(U3-BOUT2)") (class "Default")
      (node (ref "U3") (pin "5") (pinfunction "BOUT2_5") (pintype "bidirectional"))
      (node (ref "X4") (pin "6") (pinfunction "M1_6") (pintype "bidirectional"))
    )
    (net (code "68") (name "Net-(U3-NFAULT)") (class "Default")
      (node (ref "MOT_FLT") (pin "C") (pinfunction "C_C") (pintype "passive"))
      (node (ref "U3") (pin "8") (pinfunction "NFAULT_8") (pintype "bidirectional"))
    )
    (net (code "69") (name "Net-(U3-VCP)") (class "Default")
      (node (ref "C15") (pin "2") (pinfunction "2_2") (pintype "passive"))
      (node (ref "U3") (pin "11") (pinfunction "VCP_11") (pintype "bidirectional"))
    )
    (net (code "70") (name "Net-(U3-VINT)") (class "Default")
      (node (ref "C16") (pin "1") (pinfunction "1_1") (pintype "passive"))
      (node (ref "U3") (pin "14") (pinfunction "VINT_14") (pintype "bidirectional"))
    )
    (net (code "71") (name "Net-(X1A-S)") (class "Default")
      (node (ref "X1") (pin "1") (pinfunction "S_1") (pintype "passive"))
      (node (ref "X2") (pin "2") (pinfunction "S_2") (pintype "passive"))
    )
    (net (code "72") (name "RESET") (class "Default")
      (node (ref "BUS2") (pin "2") (pinfunction "2_2") (pintype "passive"))
      (node (ref "C6") (pin "1") (pinfunction "1_1") (pintype "passive"))
      (node (ref "IC2") (pin "4") (pinfunction "RESET_4") (pintype "input"))
      (node (ref "ISP") (pin "5") (pinfunction "RST_5") (pintype "output"))
      (node (ref "R7") (pin "1") (pinfunction "1_1") (pintype "passive"))
      (node (ref "SW3") (pin "1") (pinfunction "1_1") (pintype "bidirectional"))
      (node (ref "U3") (pin "1") (pinfunction "NSLEEP_1") (pintype "bidirectional"))
    )
    (net (code "73") (name "RXD") (class "Default")
      (node (ref "BUS2") (pin "6") (pinfunction "6_6") (pintype "passive"))
      (node (ref "IC2") (pin "9") (pinfunction "(PCINT24/RXD0)PD0_9") (pintype "bidirectional"))
      (node (ref "U1") (pin "4") (pinfunction "TXD_4") (pintype "bidirectional"))
    )
    (net (code "74") (name "SCK") (class "Default")
      (node (ref "BUS2") (pin "3") (pinfunction "3_3") (pintype "passive"))
      (node (ref "IC2") (pin "3") (pinfunction "(PCINT15/SCK)PB7_3") (pintype "bidirectional"))
      (node (ref "ISP") (pin "3") (pinfunction "SCK_3") (pintype "output"))
    )
    (net (code "75") (name "SCL") (class "Default")
      (node (ref "BUS1") (pin "4") (pinfunction "4_4") (pintype "passive"))
      (node (ref "IC2") (pin "19") (pinfunction "(PCINT16/SCL)PC0_19") (pintype "output"))
      (node (ref "R11") (pin "1") (pinfunction "1_1") (pintype "passive"))
    )
    (net (code "76") (name "SDA") (class "Default")
      (node (ref "BUS1") (pin "5") (pinfunction "5_5") (pintype "passive"))
      (node (ref "IC2") (pin "20") (pinfunction "(PCINT17/SDA)PC1_20") (pintype "output"))
      (node (ref "R10") (pin "1") (pinfunction "1_1") (pintype "passive"))
    )
    (net (code "77") (name "START") (class "Default")
      (node (ref "BUS1") (pin "3") (pinfunction "3_3") (pintype "passive"))
      (node (ref "IC2") (pin "44") (pinfunction "(PCINT12/OC0B/~{SS})PB4_44") (pintype "bidirectional"))
      (node (ref "SW1") (pin "4") (pinfunction "4_4") (pintype "bidirectional"))
    )
    (net (code "78") (name "TXD") (class "Default")
      (node (ref "BUS2") (pin "7") (pinfunction "7_7") (pintype "passive"))
      (node (ref "IC2") (pin "10") (pinfunction "(PCINT25/TXD0)PD1_10") (pintype "bidirectional"))
      (node (ref "R14") (pin "2") (pinfunction "2_2") (pintype "passive"))
    )
    (net (code "79") (name "TXD_3V3") (class "Default")
      (node (ref "R14") (pin "1") (pinfunction "1_1") (pintype "passive"))
      (node (ref "R15") (pin "2") (pinfunction "2_2") (pintype "passive"))
      (node (ref "U1") (pin "5") (pinfunction "RXD_5") (pintype "bidirectional"))
    )
    (net (code "80") (name "USER") (class "Default")
      (node (ref "IC2") (pin "43") (pinfunction "(PCINT11/OC0A/AIN1)PB3_43") (pintype "bidirectional"))
      (node (ref "SW2") (pin "4") (pinfunction "4_4") (pintype "bidirectional"))
    )
    (net (code "81") (name "V+") (class "Default")
      (node (ref "BUS1") (pin "2") (pinfunction "2_2") (pintype "passive"))
      (node (ref "C1") (pin "+") (pinfunction "+_+") (pintype "passive"))
      (node (ref "C13") (pin "1") (pinfunction "1_1") (pintype "passive"))
      (node (ref "C14") (pin "1") (pinfunction "1_1") (pintype "passive"))
      (node (ref "C15") (pin "1") (pinfunction "1_1") (pintype "passive"))
      (node (ref "C2") (pin "1") (pinfunction "1_1") (pintype "passive"))
      (node (ref "D1") (pin "C") (pinfunction "C_C") (pintype "passive"))
      (node (ref "IC1") (pin "3") (pinfunction "VIN_3") (pintype "input"))
      (node (ref "R1") (pin "2") (pinfunction "2_2") (pintype "passive"))
      (node (ref "R2") (pin "2") (pinfunction "2_2") (pintype "passive"))
      (node (ref "R29") (pin "1") (pinfunction "1_1") (pintype "passive"))
      (node (ref "R3") (pin "2") (pinfunction "2_2") (pintype "passive"))
      (node (ref "U3") (pin "12") (pinfunction "VM_12") (pintype "bidirectional"))
    )
    (net (code "82") (name "VBAT") (class "Default")
      (node (ref "IC2") (pin "35") (pinfunction "(PCINT2/ADC2)PA2_35") (pintype "bidirectional"))
      (node (ref "R3") (pin "1") (pinfunction "1_1") (pintype "passive"))
      (node (ref "R5") (pin "2") (pinfunction "2_2") (pintype "passive"))
    )
    (net (code "83") (name "VDD") (class "Default")
      (node (ref "IC9") (pin "5") (pinfunction "VDD_5") (pintype "power_in"))
    )
    (net (code "84") (name "VSS") (class "Default")
      (node (ref "IC9") (pin "15") (pinfunction "VSS_15") (pintype "power_in"))
    )
    (net (code "85") (name "unconnected-(IC9-A0-Pad6)") (class "Default")
      (node (ref "IC9") (pin "6") (pinfunction "A0_6") (pintype "input"))
    )
    (net (code "86") (name "unconnected-(IC9-A1-Pad7)") (class "Default")
      (node (ref "IC9") (pin "7") (pinfunction "A1_7") (pintype "input"))
    )
    (net (code "87") (name "unconnected-(IC9-A2-Pad9)") (class "Default")
      (node (ref "IC9") (pin "9") (pinfunction "A2_9") (pintype "input"))
    )
    (net (code "88") (name "unconnected-(IC9-SCL-Pad2)") (class "Default")
      (node (ref "IC9") (pin "2") (pinfunction "SCL_2") (pintype "input"))
    )
    (net (code "89") (name "unconnected-(IC9-SDA-Pad4)") (class "Default")
      (node (ref "IC9") (pin "4") (pinfunction "SDA_4") (pintype "bidirectional"))
    )
    (net (code "90") (name "unconnected-(IC9-~{INT}-Pad1)") (class "Default")
      (node (ref "IC9") (pin "1") (pinfunction "~{INT}_1") (pintype "output"))
    )
    (net (code "91") (name "unconnected-(S1-O-Pad1)") (class "Default")
      (node (ref "S1") (pin "1") (pinfunction "O_1") (pintype "passive"))
    )
    (net (code "92") (name "unconnected-(SW1-Pad2)") (class "Default")
      (node (ref "SW1") (pin "2") (pinfunction "2_2") (pintype "bidirectional"))
    )
    (net (code "93") (name "unconnected-(SW1-Pad3)") (class "Default")
      (node (ref "SW1") (pin "3") (pinfunction "3_3") (pintype "bidirectional"))
    )
    (net (code "94") (name "unconnected-(SW1-Pad5)") (class "Default")
      (node (ref "SW1") (pin "5") (pinfunction "5_5") (pintype "bidirectional"))
    )
    (net (code "95") (name "unconnected-(SW2-Pad2)") (class "Default")
      (node (ref "SW2") (pin "2") (pinfunction "2_2") (pintype "bidirectional"))
    )
    (net (code "96") (name "unconnected-(SW2-Pad3)") (class "Default")
      (node (ref "SW2") (pin "3") (pinfunction "3_3") (pintype "bidirectional"))
    )
    (net (code "97") (name "unconnected-(SW2-Pad5)") (class "Default")
      (node (ref "SW2") (pin "5") (pinfunction "5_5") (pintype "bidirectional"))
    )
    (net (code "98") (name "unconnected-(SW3-Pad2)") (class "Default")
      (node (ref "SW3") (pin "2") (pinfunction "2_2") (pintype "bidirectional"))
    )
    (net (code "99") (name "unconnected-(SW3-Pad3)") (class "Default")
      (node (ref "SW3") (pin "3") (pinfunction "3_3") (pintype "bidirectional"))
    )
    (net (code "100") (name "unconnected-(SW3-Pad5)") (class "Default")
      (node (ref "SW3") (pin "5") (pinfunction "5_5") (pintype "bidirectional"))
    )
    (net (code "101") (name "unconnected-(U1-EN-Pad1)") (class "Default")
      (node (ref "U1") (pin "1") (pinfunction "EN_1") (pintype "bidirectional"))
    )
    (net (code "102") (name "unconnected-(U1-STATE-Pad6)") (class "Default")
      (node (ref "U1") (pin "6") (pinfunction "STATE_6") (pintype "bidirectional"))
    )
    (net (code "103") (name "unconnected-(X3-A-Pad3)") (class "Default")
      (node (ref "X3") (pin "3") (pinfunction "A_3") (pintype "bidirectional"))
    )
    (net (code "104") (name "unconnected-(X3-B-Pad2)") (class "Default")
      (node (ref "X3") (pin "2") (pinfunction "B_2") (pintype "bidirectional"))
    )
    (net (code "105") (name "unconnected-(X3-GND-Pad1)") (class "Default")
      (node (ref "X3") (pin "1") (pinfunction "GND_1") (pintype "bidirectional"))
    )
    (net (code "106") (name "unconnected-(X3-VCC-Pad4)") (class "Default")
      (node (ref "X3") (pin "4") (pinfunction "VCC_4") (pintype "bidirectional"))
    )
    (net (code "107") (name "unconnected-(X4-A-Pad3)") (class "Default")
      (node (ref "X4") (pin "3") (pinfunction "A_3") (pintype "bidirectional"))
    )
    (net (code "108") (name "unconnected-(X4-B-Pad2)") (class "Default")
      (node (ref "X4") (pin "2") (pinfunction "B_2") (pintype "bidirectional"))
    )
    (net (code "109") (name "unconnected-(X4-GND-Pad1)") (class "Default")
      (node (ref "X4") (pin "1") (pinfunction "GND_1") (pintype "bidirectional"))
    )
    (net (code "110") (name "unconnected-(X4-VCC-Pad4)") (class "Default")
      (node (ref "X4") (pin "4") (pinfunction "VCC_4") (pintype "bidirectional"))
    )
  )
)
